# Safety_2019_V_3_0_Enable.net
KiCad netlist of a schematic drawn in Altium Designer
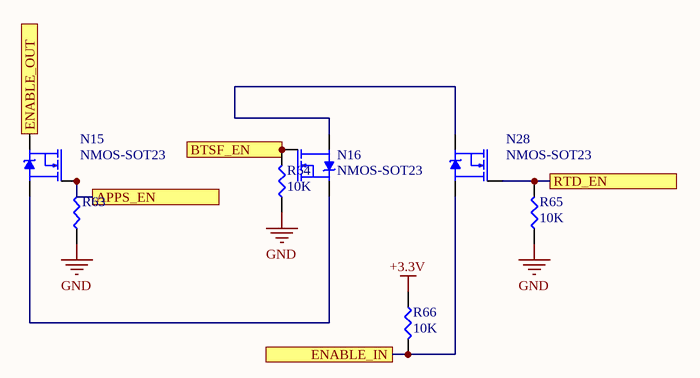
[diagram p0: Safety_2019_V_3_0_Enable.SchDoc]

(export (version "E")
  (design (tool "Eeschema 10.0.6"))
  (components
    (comp (ref "N15")
      (value "NMOS-SOT23")
      (footprint "SOT23")
      (libsource (lib "ife19_Elec_Library") (part "NMOS-SOT23"))
    )
    (comp (ref "N16")
      (value "NMOS-SOT23")
      (footprint "SOT23")
      (libsource (lib "ife19_Elec_Library") (part "NMOS-SOT23"))
    )
    (comp (ref "N28")
      (value "NMOS-SOT23")
      (footprint "SOT23")
      (libsource (lib "ife19_Elec_Library") (part "NMOS-SOT23"))
    )
    (comp (ref "R63")
      (value "~")
      (footprint "RES-0603")
      (libsource (lib "ife19_Elec_Library") (part "RES-0603"))
    )
    (comp (ref "R64")
      (value "10K")
      (footprint "RES-0603")
      (libsource (lib "ife19_Elec_Library") (part "RES-0603"))
    )
    (comp (ref "R65")
      (value "10K")
      (footprint "RES-0603")
      (libsource (lib "ife19_Elec_Library") (part "RES-0603"))
    )
    (comp (ref "R66")
      (value "10K")
      (footprint "RES-0603")
      (libsource (lib "ife19_Elec_Library") (part "RES-0603"))
    )
  )
  (nets
    (net (code "1") (name "+3.3V") (class "Default")
      (node (ref "R66") (pin "1") (pinfunction "1_1") (pintype "passive"))
    )
    (net (code "2") (name "/APPS_EN") (class "Default")
      (node (ref "N15") (pin "1") (pinfunction "G_1") (pintype "passive"))
      (node (ref "R63") (pin "2") (pinfunction "2_2") (pintype "passive"))
    )
    (net (code "3") (name "/BTSF_EN") (class "Default")
      (node (ref "N16") (pin "1") (pinfunction "G_1") (pintype "passive"))
      (node (ref "R64") (pin "2") (pinfunction "2_2") (pintype "passive"))
    )
    (net (code "4") (name "/ENABLE_IN") (class "Default")
      (node (ref "N28") (pin "2") (pinfunction "S_2") (pintype "passive"))
      (node (ref "R66") (pin "2") (pinfunction "2_2") (pintype "passive"))
    )
    (net (code "5") (name "/ENABLE_OUT") (class "Default")
      (node (ref "N15") (pin "3") (pinfunction "D_3") (pintype "passive"))
    )
    (net (code "6") (name "/RTD_EN") (class "Default")
      (node (ref "N28") (pin "1") (pinfunction "G_1") (pintype "passive"))
      (node (ref "R65") (pin "2") (pinfunction "2_2") (pintype "passive"))
    )
    (net (code "7") (name "GND") (class "Default")
      (node (ref "R63") (pin "1") (pinfunction "1_1") (pintype "passive"))
      (node (ref "R64") (pin "1") (pinfunction "1_1") (pintype "passive"))
      (node (ref "R65") (pin "1") (pinfunction "1_1") (pintype "passive"))
    )
    (net (code "8") (name "Net-(N15-S)") (class "Default")
      (node (ref "N15") (pin "2") (pinfunction "S_2") (pintype "passive"))
      (node (ref "N16") (pin "3") (pinfunction "D_3") (pintype "passive"))
    )
    (net (code "9") (name "Net-(N16-S)") (class "Default")
      (node (ref "N16") (pin "2") (pinfunction "S_2") (pintype "passive"))
      (node (ref "N28") (pin "3") (pinfunction "D_3") (pintype "passive"))
    )
  )
)
